# M502B.net
KiCad netlist of a schematic drawn in EAGLE
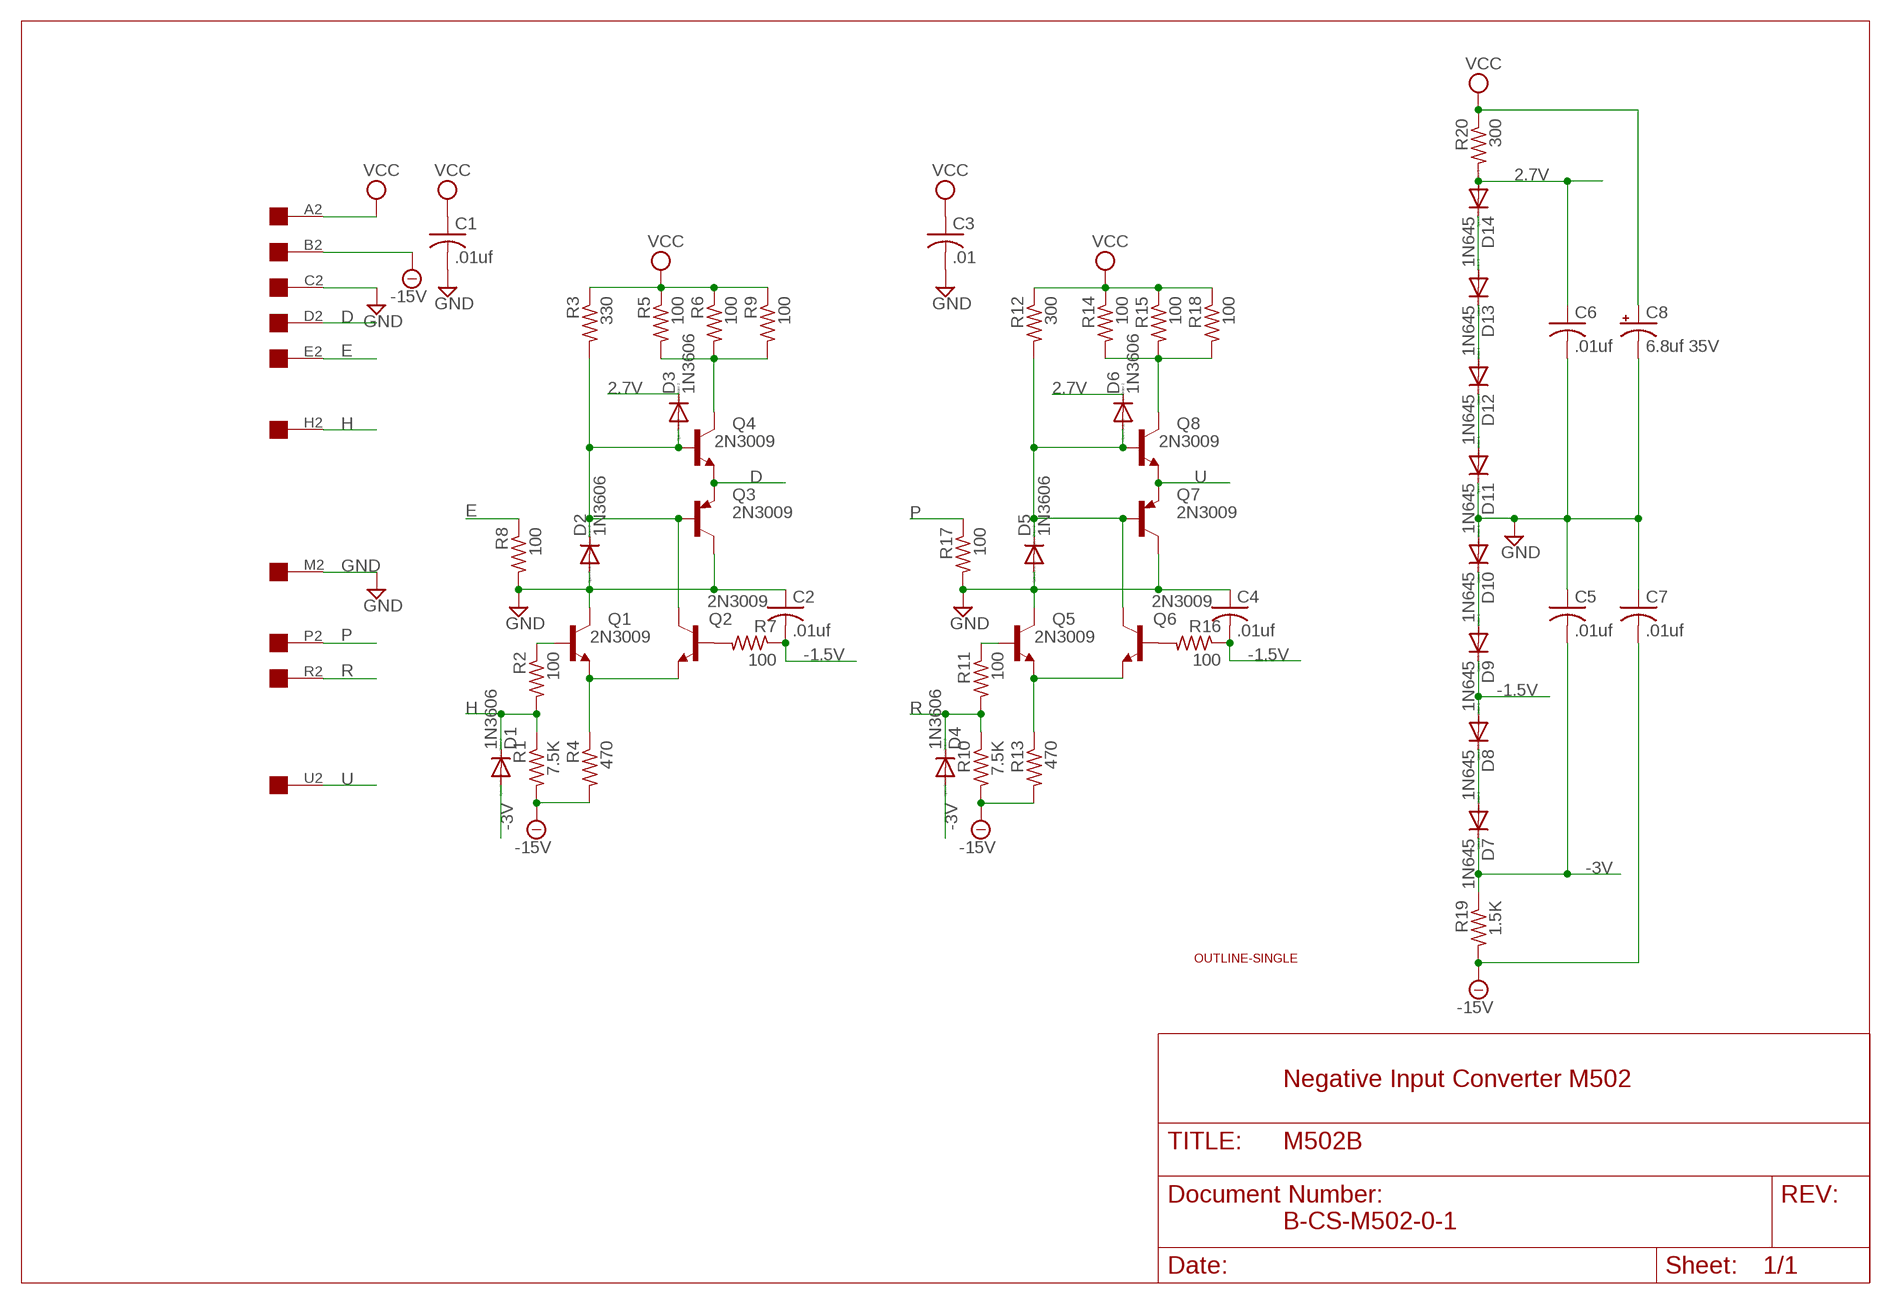
[diagram p0: schematic, sheet 1]

(export (version "E")
  (design (tool "Eeschema 10.0.6"))
  (components
    (comp (ref "C1")
      (value ".01uf")
      (footprint "eagle-import:C050-025X075")
      (libsource (lib "eagle-import") (part "C-US050-025X075"))
    )
    (comp (ref "C2")
      (value ".01uf")
      (footprint "eagle-import:C050-025X075")
      (libsource (lib "eagle-import") (part "C-US050-025X075"))
    )
    (comp (ref "C3")
      (value ".01")
      (footprint "eagle-import:C050-025X075")
      (libsource (lib "eagle-import") (part "C-US050-025X075"))
    )
    (comp (ref "C4")
      (value ".01uf")
      (footprint "eagle-import:C050-025X075")
      (libsource (lib "eagle-import") (part "C-US050-025X075"))
    )
    (comp (ref "C5")
      (value ".01uf")
      (footprint "eagle-import:C050-025X075")
      (libsource (lib "eagle-import") (part "C-US050-025X075"))
    )
    (comp (ref "C6")
      (value ".01uf")
      (footprint "eagle-import:C050-025X075")
      (libsource (lib "eagle-import") (part "C-US050-025X075"))
    )
    (comp (ref "C7")
      (value ".01uf")
      (footprint "eagle-import:C050-025X075")
      (libsource (lib "eagle-import") (part "C-US050-025X075"))
    )
    (comp (ref "C8")
      (value "6.8uf 35V")
      (footprint "eagle-import:E15-5")
      (libsource (lib "eagle-import") (part "CPOL-USE15-5AXIAL"))
    )
    (comp (ref "D1")
      (value "1N3606")
      (footprint "eagle-import:DO41-10")
      (libsource (lib "eagle-import") (part "1N4004"))
    )
    (comp (ref "D2")
      (value "1N3606")
      (footprint "eagle-import:DO41-10")
      (libsource (lib "eagle-import") (part "1N4004"))
    )
    (comp (ref "D3")
      (value "1N3606")
      (footprint "eagle-import:DO41-10")
      (libsource (lib "eagle-import") (part "1N4004"))
    )
    (comp (ref "D4")
      (value "1N3606")
      (footprint "eagle-import:DO41-10")
      (libsource (lib "eagle-import") (part "1N4004"))
    )
    (comp (ref "D5")
      (value "1N3606")
      (footprint "eagle-import:DO41-10")
      (libsource (lib "eagle-import") (part "1N4004"))
    )
    (comp (ref "D6")
      (value "1N3606")
      (footprint "eagle-import:DO41-10")
      (libsource (lib "eagle-import") (part "1N4004"))
    )
    (comp (ref "D7")
      (value "1N645")
      (footprint "eagle-import:DO41-10")
      (libsource (lib "eagle-import") (part "1N4004"))
    )
    (comp (ref "D8")
      (value "1N645")
      (footprint "eagle-import:DO41-10")
      (libsource (lib "eagle-import") (part "1N4004"))
    )
    (comp (ref "D9")
      (value "1N645")
      (footprint "eagle-import:DO41-10")
      (libsource (lib "eagle-import") (part "1N4004"))
    )
    (comp (ref "D10")
      (value "1N645")
      (footprint "eagle-import:DO41-10")
      (libsource (lib "eagle-import") (part "1N4004"))
    )
    (comp (ref "D11")
      (value "1N645")
      (footprint "eagle-import:DO41-10")
      (libsource (lib "eagle-import") (part "1N4004"))
    )
    (comp (ref "D12")
      (value "1N645")
      (footprint "eagle-import:DO41-10")
      (libsource (lib "eagle-import") (part "1N4004"))
    )
    (comp (ref "D13")
      (value "1N645")
      (footprint "eagle-import:DO41-10")
      (libsource (lib "eagle-import") (part "1N4004"))
    )
    (comp (ref "D14")
      (value "1N645")
      (footprint "eagle-import:DO41-10")
      (libsource (lib "eagle-import") (part "1N4004"))
    )
    (comp (ref "Q1")
      (value "2N3009")
      (footprint "eagle-import:TO39")
      (libsource (lib "eagle-import") (part "2N1711"))
    )
    (comp (ref "Q2")
      (value "2N3009")
      (footprint "eagle-import:TO39")
      (libsource (lib "eagle-import") (part "2N1711"))
    )
    (comp (ref "Q3")
      (value "2N3009")
      (footprint "eagle-import:TO39")
      (libsource (lib "eagle-import") (part "2N5415"))
    )
    (comp (ref "Q4")
      (value "2N3009")
      (footprint "eagle-import:TO39")
      (libsource (lib "eagle-import") (part "2N1711"))
    )
    (comp (ref "Q5")
      (value "2N3009")
      (footprint "eagle-import:TO39")
      (libsource (lib "eagle-import") (part "2N1711"))
    )
    (comp (ref "Q6")
      (value "2N3009")
      (footprint "eagle-import:TO39")
      (libsource (lib "eagle-import") (part "2N1711"))
    )
    (comp (ref "Q7")
      (value "2N3009")
      (footprint "eagle-import:TO39")
      (libsource (lib "eagle-import") (part "2N5415"))
    )
    (comp (ref "Q8")
      (value "2N3009")
      (footprint "eagle-import:TO39")
      (libsource (lib "eagle-import") (part "2N1711"))
    )
    (comp (ref "R1")
      (value "7.5K")
      (footprint "eagle-import:0207_10")
      (libsource (lib "eagle-import") (part "R-US_0207/10"))
    )
    (comp (ref "R2")
      (value "100")
      (footprint "eagle-import:0207_10")
      (libsource (lib "eagle-import") (part "R-US_0207/10"))
    )
    (comp (ref "R3")
      (value "330")
      (footprint "eagle-import:0207_10")
      (libsource (lib "eagle-import") (part "R-US_0207/10"))
    )
    (comp (ref "R4")
      (value "470")
      (footprint "eagle-import:0207_10")
      (libsource (lib "eagle-import") (part "R-US_0207/10"))
    )
    (comp (ref "R5")
      (value "100")
      (footprint "eagle-import:0207_10")
      (libsource (lib "eagle-import") (part "R-US_0207/10"))
    )
    (comp (ref "R6")
      (value "100")
      (footprint "eagle-import:0207_10")
      (libsource (lib "eagle-import") (part "R-US_0207/10"))
    )
    (comp (ref "R7")
      (value "100")
      (footprint "eagle-import:0207_10")
      (libsource (lib "eagle-import") (part "R-US_0207/10"))
    )
    (comp (ref "R8")
      (value "100")
      (footprint "eagle-import:0207_10")
      (libsource (lib "eagle-import") (part "R-US_0207/10"))
    )
    (comp (ref "R9")
      (value "100")
      (footprint "eagle-import:0207_10")
      (libsource (lib "eagle-import") (part "R-US_0207/10"))
    )
    (comp (ref "R10")
      (value "7.5K")
      (footprint "eagle-import:0207_10")
      (libsource (lib "eagle-import") (part "R-US_0207/10"))
    )
    (comp (ref "R11")
      (value "100")
      (footprint "eagle-import:0207_10")
      (libsource (lib "eagle-import") (part "R-US_0207/10"))
    )
    (comp (ref "R12")
      (value "300")
      (footprint "eagle-import:0207_10")
      (libsource (lib "eagle-import") (part "R-US_0207/10"))
    )
    (comp (ref "R13")
      (value "470")
      (footprint "eagle-import:0207_10")
      (libsource (lib "eagle-import") (part "R-US_0207/10"))
    )
    (comp (ref "R14")
      (value "100")
      (footprint "eagle-import:0207_10")
      (libsource (lib "eagle-import") (part "R-US_0207/10"))
    )
    (comp (ref "R15")
      (value "100")
      (footprint "eagle-import:0207_10")
      (libsource (lib "eagle-import") (part "R-US_0207/10"))
    )
    (comp (ref "R16")
      (value "100")
      (footprint "eagle-import:0207_10")
      (libsource (lib "eagle-import") (part "R-US_0207/10"))
    )
    (comp (ref "R17")
      (value "100")
      (footprint "eagle-import:0207_10")
      (libsource (lib "eagle-import") (part "R-US_0207/10"))
    )
    (comp (ref "R18")
      (value "100")
      (footprint "eagle-import:0207_10")
      (libsource (lib "eagle-import") (part "R-US_0207/10"))
    )
    (comp (ref "R19")
      (value "1.5K")
      (footprint "eagle-import:0207_10")
      (libsource (lib "eagle-import") (part "R-US_0207/10"))
    )
    (comp (ref "R20")
      (value "300")
      (footprint "eagle-import:0207_10")
      (libsource (lib "eagle-import") (part "R-US_0207/10"))
    )
    (comp (ref "U$1")
      (value "EDGE-1")
      (footprint "eagle-import:EDGE-CON1")
      (libsource (lib "eagle-import") (part "EDGE-1"))
    )
    (comp (ref "U$2")
      (value "OUTLINE-SINGLE")
      (footprint "eagle-import:SINGLE")
      (libsource (lib "eagle-import") (part "OUTLINE-SINGLE"))
    )
  )
  (nets
    (net (code "1") (name "-15V") (class "Default")
      (node (ref "C7") (pin "2") (pinfunction "2_2") (pintype "passive"))
      (node (ref "R1") (pin "2") (pinfunction "2_2") (pintype "passive"))
      (node (ref "R10") (pin "2") (pinfunction "2_2") (pintype "passive"))
      (node (ref "R13") (pin "2") (pinfunction "2_2") (pintype "passive"))
      (node (ref "R19") (pin "2") (pinfunction "2_2") (pintype "passive"))
      (node (ref "R4") (pin "2") (pinfunction "2_2") (pintype "passive"))
      (node (ref "U$1") (pin "B2") (pinfunction "1_B2") (pintype "bidirectional"))
    )
    (net (code "2") (name "/-1.5V") (class "Default")
      (node (ref "C2") (pin "2") (pinfunction "2_2") (pintype "passive"))
      (node (ref "C4") (pin "2") (pinfunction "2_2") (pintype "passive"))
      (node (ref "D8") (pin "A") (pinfunction "A_A") (pintype "passive"))
      (node (ref "D9") (pin "C") (pinfunction "C_C") (pintype "passive"))
      (node (ref "R16") (pin "1") (pinfunction "1_1") (pintype "passive"))
      (node (ref "R7") (pin "1") (pinfunction "1_1") (pintype "passive"))
    )
    (net (code "3") (name "/-3V") (class "Default")
      (node (ref "C5") (pin "2") (pinfunction "2_2") (pintype "passive"))
      (node (ref "D1") (pin "A") (pinfunction "A_A") (pintype "passive"))
      (node (ref "D4") (pin "A") (pinfunction "A_A") (pintype "passive"))
      (node (ref "D7") (pin "C") (pinfunction "C_C") (pintype "passive"))
      (node (ref "R19") (pin "1") (pinfunction "1_1") (pintype "passive"))
    )
    (net (code "4") (name "/2.7V") (class "Default")
      (node (ref "C6") (pin "1") (pinfunction "1_1") (pintype "passive"))
      (node (ref "D14") (pin "A") (pinfunction "A_A") (pintype "passive"))
      (node (ref "D3") (pin "C") (pinfunction "C_C") (pintype "passive"))
      (node (ref "D6") (pin "C") (pinfunction "C_C") (pintype "passive"))
      (node (ref "R20") (pin "2") (pinfunction "2_2") (pintype "passive"))
    )
    (net (code "5") (name "/D") (class "Default")
      (node (ref "Q3") (pin "1") (pinfunction "E_1") (pintype "passive"))
      (node (ref "Q4") (pin "1") (pinfunction "E_1") (pintype "passive"))
      (node (ref "U$1") (pin "D2") (pinfunction "1_D2") (pintype "bidirectional"))
    )
    (net (code "6") (name "/E") (class "Default")
      (node (ref "R8") (pin "1") (pinfunction "1_1") (pintype "passive"))
      (node (ref "U$1") (pin "E2") (pinfunction "1_E2") (pintype "bidirectional"))
    )
    (net (code "7") (name "/H") (class "Default")
      (node (ref "D1") (pin "C") (pinfunction "C_C") (pintype "passive"))
      (node (ref "R1") (pin "1") (pinfunction "1_1") (pintype "passive"))
      (node (ref "R2") (pin "2") (pinfunction "2_2") (pintype "passive"))
      (node (ref "U$1") (pin "H2") (pinfunction "1_H2") (pintype "bidirectional"))
    )
    (net (code "8") (name "/P") (class "Default")
      (node (ref "R17") (pin "1") (pinfunction "1_1") (pintype "passive"))
      (node (ref "U$1") (pin "P2") (pinfunction "1_P2") (pintype "bidirectional"))
    )
    (net (code "9") (name "/R") (class "Default")
      (node (ref "D4") (pin "C") (pinfunction "C_C") (pintype "passive"))
      (node (ref "R10") (pin "1") (pinfunction "1_1") (pintype "passive"))
      (node (ref "R11") (pin "2") (pinfunction "2_2") (pintype "passive"))
      (node (ref "U$1") (pin "R2") (pinfunction "1_R2") (pintype "bidirectional"))
    )
    (net (code "10") (name "/U") (class "Default")
      (node (ref "Q7") (pin "1") (pinfunction "E_1") (pintype "passive"))
      (node (ref "Q8") (pin "1") (pinfunction "E_1") (pintype "passive"))
      (node (ref "U$1") (pin "U2") (pinfunction "1_U2") (pintype "bidirectional"))
    )
    (net (code "11") (name "GND") (class "Default")
      (node (ref "C1") (pin "2") (pinfunction "2_2") (pintype "passive"))
      (node (ref "C2") (pin "1") (pinfunction "1_1") (pintype "passive"))
      (node (ref "C3") (pin "2") (pinfunction "2_2") (pintype "passive"))
      (node (ref "C4") (pin "1") (pinfunction "1_1") (pintype "passive"))
      (node (ref "C5") (pin "1") (pinfunction "1_1") (pintype "passive"))
      (node (ref "C6") (pin "2") (pinfunction "2_2") (pintype "passive"))
      (node (ref "C7") (pin "1") (pinfunction "1_1") (pintype "passive"))
      (node (ref "C8") (pin "-") (pinfunction "-_-") (pintype "passive"))
      (node (ref "D10") (pin "A") (pinfunction "A_A") (pintype "passive"))
      (node (ref "D11") (pin "C") (pinfunction "C_C") (pintype "passive"))
      (node (ref "D2") (pin "A") (pinfunction "A_A") (pintype "passive"))
      (node (ref "D5") (pin "A") (pinfunction "A_A") (pintype "passive"))
      (node (ref "Q1") (pin "3") (pinfunction "C_3") (pintype "passive"))
      (node (ref "Q3") (pin "3") (pinfunction "C_3") (pintype "passive"))
      (node (ref "Q5") (pin "3") (pinfunction "C_3") (pintype "passive"))
      (node (ref "Q7") (pin "3") (pinfunction "C_3") (pintype "passive"))
      (node (ref "R17") (pin "2") (pinfunction "2_2") (pintype "passive"))
      (node (ref "R8") (pin "2") (pinfunction "2_2") (pintype "passive"))
      (node (ref "U$1") (pin "C2") (pinfunction "1_C2") (pintype "bidirectional"))
      (node (ref "U$1") (pin "M2") (pinfunction "1_M2") (pintype "bidirectional"))
    )
    (net (code "12") (name "Net-(D7-PadA)") (class "Default")
      (node (ref "D7") (pin "A") (pinfunction "A_A") (pintype "passive"))
      (node (ref "D8") (pin "C") (pinfunction "C_C") (pintype "passive"))
    )
    (net (code "13") (name "Net-(D10-PadC)") (class "Default")
      (node (ref "D10") (pin "C") (pinfunction "C_C") (pintype "passive"))
      (node (ref "D9") (pin "A") (pinfunction "A_A") (pintype "passive"))
    )
    (net (code "14") (name "Net-(D11-PadA)") (class "Default")
      (node (ref "D11") (pin "A") (pinfunction "A_A") (pintype "passive"))
      (node (ref "D12") (pin "C") (pinfunction "C_C") (pintype "passive"))
    )
    (net (code "15") (name "Net-(D12-PadA)") (class "Default")
      (node (ref "D12") (pin "A") (pinfunction "A_A") (pintype "passive"))
      (node (ref "D13") (pin "C") (pinfunction "C_C") (pintype "passive"))
    )
    (net (code "16") (name "Net-(D13-PadA)") (class "Default")
      (node (ref "D13") (pin "A") (pinfunction "A_A") (pintype "passive"))
      (node (ref "D14") (pin "C") (pinfunction "C_C") (pintype "passive"))
    )
    (net (code "17") (name "Net-(Q1-B)") (class "Default")
      (node (ref "Q1") (pin "2") (pinfunction "B_2") (pintype "passive"))
      (node (ref "R2") (pin "1") (pinfunction "1_1") (pintype "passive"))
    )
    (net (code "18") (name "Net-(Q1-E)") (class "Default")
      (node (ref "Q1") (pin "1") (pinfunction "E_1") (pintype "passive"))
      (node (ref "Q2") (pin "1") (pinfunction "E_1") (pintype "passive"))
      (node (ref "R4") (pin "1") (pinfunction "1_1") (pintype "passive"))
    )
    (net (code "19") (name "Net-(Q2-B)") (class "Default")
      (node (ref "Q2") (pin "2") (pinfunction "B_2") (pintype "passive"))
      (node (ref "R7") (pin "2") (pinfunction "2_2") (pintype "passive"))
    )
    (net (code "20") (name "Net-(Q2-C)") (class "Default")
      (node (ref "D2") (pin "C") (pinfunction "C_C") (pintype "passive"))
      (node (ref "D3") (pin "A") (pinfunction "A_A") (pintype "passive"))
      (node (ref "Q2") (pin "3") (pinfunction "C_3") (pintype "passive"))
      (node (ref "Q3") (pin "2") (pinfunction "B_2") (pintype "passive"))
      (node (ref "Q4") (pin "2") (pinfunction "B_2") (pintype "passive"))
      (node (ref "R3") (pin "2") (pinfunction "2_2") (pintype "passive"))
    )
    (net (code "21") (name "Net-(Q4-C)") (class "Default")
      (node (ref "Q4") (pin "3") (pinfunction "C_3") (pintype "passive"))
      (node (ref "R5") (pin "2") (pinfunction "2_2") (pintype "passive"))
      (node (ref "R6") (pin "2") (pinfunction "2_2") (pintype "passive"))
      (node (ref "R9") (pin "2") (pinfunction "2_2") (pintype "passive"))
    )
    (net (code "22") (name "Net-(Q5-B)") (class "Default")
      (node (ref "Q5") (pin "2") (pinfunction "B_2") (pintype "passive"))
      (node (ref "R11") (pin "1") (pinfunction "1_1") (pintype "passive"))
    )
    (net (code "23") (name "Net-(Q5-E)") (class "Default")
      (node (ref "Q5") (pin "1") (pinfunction "E_1") (pintype "passive"))
      (node (ref "Q6") (pin "1") (pinfunction "E_1") (pintype "passive"))
      (node (ref "R13") (pin "1") (pinfunction "1_1") (pintype "passive"))
    )
    (net (code "24") (name "Net-(Q6-B)") (class "Default")
      (node (ref "Q6") (pin "2") (pinfunction "B_2") (pintype "passive"))
      (node (ref "R16") (pin "2") (pinfunction "2_2") (pintype "passive"))
    )
    (net (code "25") (name "Net-(Q6-C)") (class "Default")
      (node (ref "D5") (pin "C") (pinfunction "C_C") (pintype "passive"))
      (node (ref "D6") (pin "A") (pinfunction "A_A") (pintype "passive"))
      (node (ref "Q6") (pin "3") (pinfunction "C_3") (pintype "passive"))
      (node (ref "Q7") (pin "2") (pinfunction "B_2") (pintype "passive"))
      (node (ref "Q8") (pin "2") (pinfunction "B_2") (pintype "passive"))
      (node (ref "R12") (pin "2") (pinfunction "2_2") (pintype "passive"))
    )
    (net (code "26") (name "Net-(Q8-C)") (class "Default")
      (node (ref "Q8") (pin "3") (pinfunction "C_3") (pintype "passive"))
      (node (ref "R14") (pin "2") (pinfunction "2_2") (pintype "passive"))
      (node (ref "R15") (pin "2") (pinfunction "2_2") (pintype "passive"))
      (node (ref "R18") (pin "2") (pinfunction "2_2") (pintype "passive"))
    )
    (net (code "27") (name "VCC") (class "Default")
      (node (ref "C1") (pin "1") (pinfunction "1_1") (pintype "passive"))
      (node (ref "C3") (pin "1") (pinfunction "1_1") (pintype "passive"))
      (node (ref "C8") (pin "+") (pinfunction "+_+") (pintype "passive"))
      (node (ref "R12") (pin "1") (pinfunction "1_1") (pintype "passive"))
      (node (ref "R14") (pin "1") (pinfunction "1_1") (pintype "passive"))
      (node (ref "R15") (pin "1") (pinfunction "1_1") (pintype "passive"))
      (node (ref "R18") (pin "1") (pinfunction "1_1") (pintype "passive"))
      (node (ref "R20") (pin "1") (pinfunction "1_1") (pintype "passive"))
      (node (ref "R3") (pin "1") (pinfunction "1_1") (pintype "passive"))
      (node (ref "R5") (pin "1") (pinfunction "1_1") (pintype "passive"))
      (node (ref "R6") (pin "1") (pinfunction "1_1") (pintype "passive"))
      (node (ref "R9") (pin "1") (pinfunction "1_1") (pintype "passive"))
      (node (ref "U$1") (pin "A2") (pinfunction "1_A2") (pintype "bidirectional"))
    )
  )
)
